# schematic.net
KiCad netlist of a schematic drawn in EAGLE
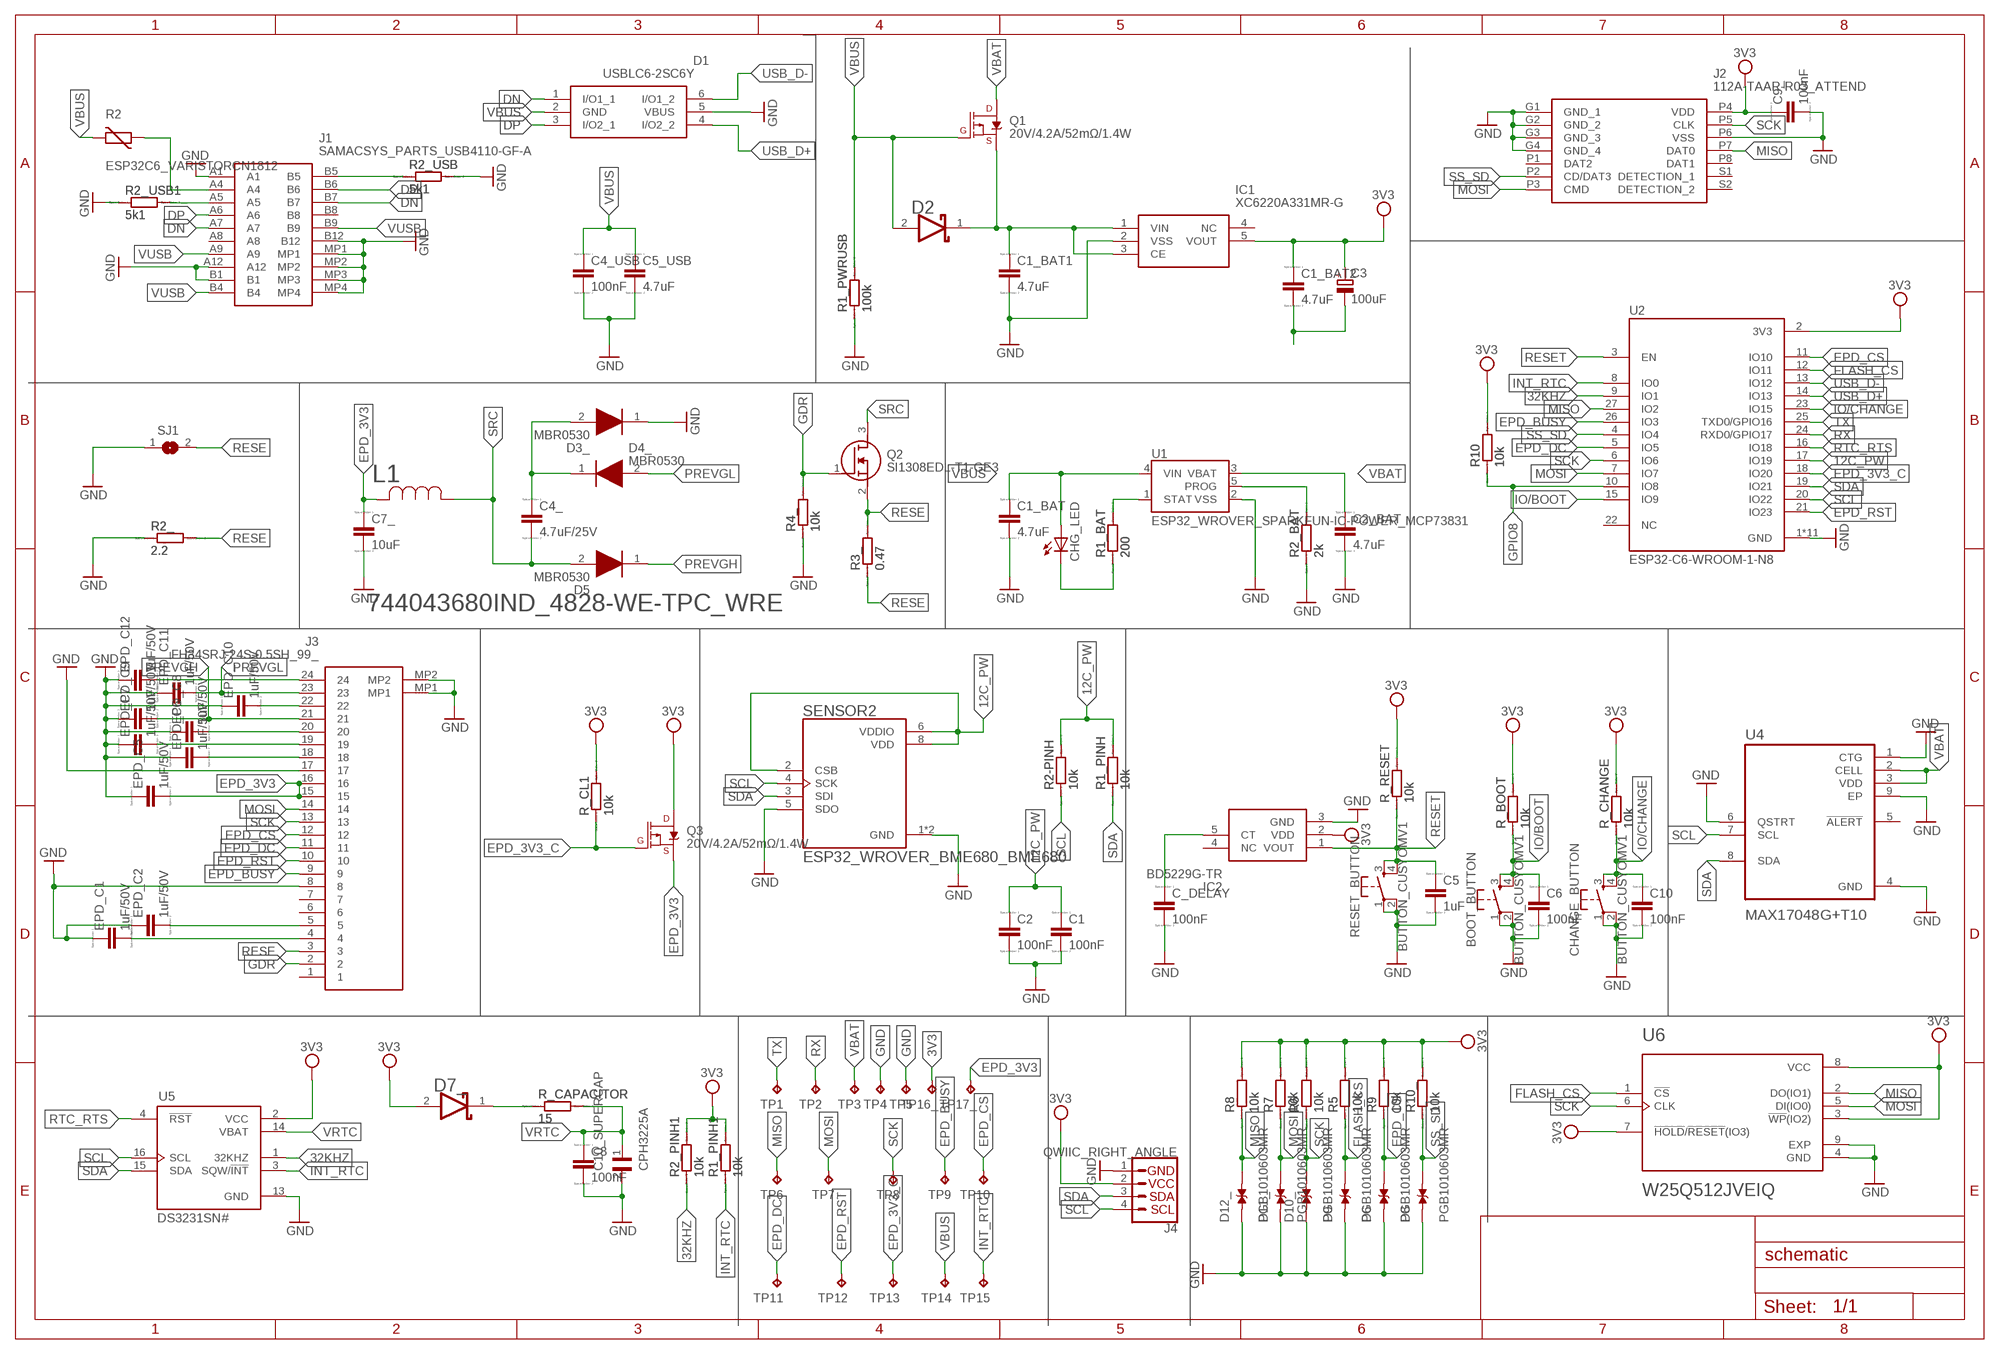
[diagram p0: schematic, sheet 1]

(export (version "E")
  (design (tool "Eeschema 10.0.6"))
  (components
    (comp (ref "BOOT_BUTTON")
      (value "BUTTON_CUSYOMV1")
      (footprint "eagle-import:MYBUTTON")
      (libsource (lib "eagle-import") (part "BUTTON_CUSYOMV1"))
    )
    (comp (ref "C1")
      (value "100nF")
      (footprint "eagle-import:EAGLE-LTSPICE_C0402")
      (libsource (lib "eagle-import") (part "EAGLE-LTSPICE_CC0402"))
    )
    (comp (ref "C1_BAT")
      (value "4.7uF")
      (footprint "eagle-import:EAGLE-LTSPICE_C0402")
      (libsource (lib "eagle-import") (part "EAGLE-LTSPICE_CC0402"))
    )
    (comp (ref "C1_BAT1")
      (value "4.7uF")
      (footprint "eagle-import:EAGLE-LTSPICE_C0402")
      (libsource (lib "eagle-import") (part "EAGLE-LTSPICE_CC0402"))
    )
    (comp (ref "C1_BAT2")
      (value "4.7uF")
      (footprint "eagle-import:EAGLE-LTSPICE_C0402")
      (libsource (lib "eagle-import") (part "EAGLE-LTSPICE_CC0402"))
    )
    (comp (ref "C2")
      (value "100nF")
      (footprint "eagle-import:EAGLE-LTSPICE_C0402")
      (libsource (lib "eagle-import") (part "EAGLE-LTSPICE_CC0402"))
    )
    (comp (ref "C2_BAT")
      (value "4.7uF")
      (footprint "eagle-import:EAGLE-LTSPICE_C0402")
      (libsource (lib "eagle-import") (part "EAGLE-LTSPICE_CC0402"))
    )
    (comp (ref "C3")
      (value "100uF")
      (footprint "eagle-import:RCL_CT3528")
      (libsource (lib "eagle-import") (part "RCL_CPOL-EUCT3528"))
    )
    (comp (ref "C4_")
      (value "4.7uF/25V")
      (footprint "eagle-import:EAGLE-LTSPICE_C0402")
      (libsource (lib "eagle-import") (part "EAGLE-LTSPICE_CC0402"))
    )
    (comp (ref "C4_USB")
      (value "100nF")
      (footprint "eagle-import:EAGLE-LTSPICE_C0402")
      (libsource (lib "eagle-import") (part "EAGLE-LTSPICE_CC0402"))
    )
    (comp (ref "C5")
      (value "1uF")
      (footprint "eagle-import:EAGLE-LTSPICE_C0402")
      (libsource (lib "eagle-import") (part "EAGLE-LTSPICE_CC0402"))
    )
    (comp (ref "C5_USB")
      (value "4.7uF")
      (footprint "eagle-import:EAGLE-LTSPICE_C0402")
      (libsource (lib "eagle-import") (part "EAGLE-LTSPICE_CC0402"))
    )
    (comp (ref "C6")
      (value "100nF")
      (footprint "eagle-import:ESP32_WROVER_EAGLE-LTSPICE_C0402")
      (libsource (lib "eagle-import") (part "ESP32_WROVER_EAGLE-LTSPICE_CC0402"))
    )
    (comp (ref "C7_")
      (value "10uF")
      (footprint "eagle-import:EAGLE-LTSPICE_C0402")
      (libsource (lib "eagle-import") (part "EAGLE-LTSPICE_CC0402"))
    )
    (comp (ref "C8")
      (value "100nF")
      (footprint "eagle-import:EAGLE-LTSPICE_C0402")
      (libsource (lib "eagle-import") (part "EAGLE-LTSPICE_CC0402"))
    )
    (comp (ref "C9_")
      (value "100nF")
      (footprint "eagle-import:ESP32_WROVER_EAGLE-LTSPICE_C0402")
      (libsource (lib "eagle-import") (part "ESP32_WROVER_EAGLE-LTSPICE_CC0402"))
    )
    (comp (ref "C10")
      (value "100nF")
      (footprint "eagle-import:ESP32_WROVER_EAGLE-LTSPICE_C0402")
      (libsource (lib "eagle-import") (part "ESP32_WROVER_EAGLE-LTSPICE_CC0402"))
    )
    (comp (ref "C10_SUPERCAP")
      (value "CPH3225A")
      (footprint "eagle-import:CAPCP3225X100N")
      (fields (field (name "MF") "Seiko Instruments"))
      (libsource (lib "eagle-import") (part "CPH3225A"))
    )
    (comp (ref "CHANGE_BUTTON")
      (value "BUTTON_CUSYOMV1")
      (footprint "eagle-import:MYBUTTON")
      (libsource (lib "eagle-import") (part "BUTTON_CUSYOMV1"))
    )
    (comp (ref "CHG_LED")
      (value "ADAFRUIT_LEDCHIP-LED0603")
      (footprint "eagle-import:ADAFRUIT_CHIP-LED0603")
      (libsource (lib "eagle-import") (part "ADAFRUIT_LEDCHIP-LED0603"))
    )
    (comp (ref "C_DELAY")
      (value "100nF")
      (footprint "eagle-import:EAGLE-LTSPICE_C0402")
      (libsource (lib "eagle-import") (part "EAGLE-LTSPICE_CC0402"))
    )
    (comp (ref "D1")
      (value "USBLC6-2SC6Y")
      (footprint "eagle-import:SOT95P280X145-6N")
      (fields (field (name "MF") "STMicroelectronics"))
      (libsource (lib "eagle-import") (part "USBLC6-2SC6Y"))
    )
    (comp (ref "D2")
      (value "ESP32_WROVER_AVX---SD0805S020S1R0_AVX_SD0805S020S1R0_0_0AVX_SD0805S020S1R0_0_0")
      (footprint "eagle-import:ESP32_WROVER_AVX---SD0805S020S1R0_AVX_SD0805S020S1R0_0")
      (fields
        (field (name "DIGIKEY_PART_NUMBER") "478-7800-1-ND")
        (field (name "MF") "AVX")
        (field (name "MOUSER_PART_NUMBER") "581-SD0805S020S1R0")
      )
      (libsource (lib "eagle-import") (part "ESP32_WROVER_AVX---SD0805S020S1R0_AVX_SD0805S020S1R0_0_0AVX_SD0805S020S1R0_0_0"))
    )
    (comp (ref "D3_")
      (value "MBR0530")
      (footprint "eagle-import:SOD3716X135N")
      (fields (field (name "MF") "ON Semiconductor"))
      (libsource (lib "eagle-import") (part "MBR0530"))
    )
    (comp (ref "D4_")
      (value "MBR0530")
      (footprint "eagle-import:SOD3716X135N")
      (fields (field (name "MF") "ON Semiconductor"))
      (libsource (lib "eagle-import") (part "MBR0530"))
    )
    (comp (ref "D5")
      (value "MBR0530")
      (footprint "eagle-import:SOD3716X135N")
      (fields (field (name "MF") "ON Semiconductor"))
      (libsource (lib "eagle-import") (part "MBR0530"))
    )
    (comp (ref "D6")
      (value "PGB1010603MR")
      (footprint "eagle-import:DIOC1608X36N")
      (fields (field (name "MF") "Littelfuse Inc."))
      (libsource (lib "eagle-import") (part "PGB1010603MR"))
    )
    (comp (ref "D7_")
      (value "ESP32_WROVER_AVX---SD0805S020S1R0_AVX_SD0805S020S1R0_0_0AVX_SD0805S020S1R0_0_0")
      (footprint "eagle-import:ESP32_WROVER_AVX---SD0805S020S1R0_AVX_SD0805S020S1R0_0")
      (fields
        (field (name "DIGIKEY_PART_NUMBER") "478-7800-1-ND")
        (field (name "MF") "AVX")
        (field (name "MOUSER_PART_NUMBER") "581-SD0805S020S1R0")
      )
      (libsource (lib "eagle-import") (part "ESP32_WROVER_AVX---SD0805S020S1R0_AVX_SD0805S020S1R0_0_0AVX_SD0805S020S1R0_0_0"))
    )
    (comp (ref "D8")
      (value "PGB1010603MR")
      (footprint "eagle-import:DIOC1608X36N")
      (fields (field (name "MF") "Littelfuse Inc."))
      (libsource (lib "eagle-import") (part "PGB1010603MR"))
    )
    (comp (ref "D9")
      (value "PGB1010603MR")
      (footprint "eagle-import:DIOC1608X36N")
      (fields (field (name "MF") "Littelfuse Inc."))
      (libsource (lib "eagle-import") (part "PGB1010603MR"))
    )
    (comp (ref "D10_")
      (value "PGB1010603MR")
      (footprint "eagle-import:DIOC1608X36N")
      (fields (field (name "MF") "Littelfuse Inc."))
      (libsource (lib "eagle-import") (part "PGB1010603MR"))
    )
    (comp (ref "D11_")
      (value "PGB1010603MR")
      (footprint "eagle-import:DIOC1608X36N")
      (fields (field (name "MF") "Littelfuse Inc."))
      (libsource (lib "eagle-import") (part "PGB1010603MR"))
    )
    (comp (ref "D12_")
      (value "PGB1010603MR")
      (footprint "eagle-import:DIOC1608X36N")
      (fields (field (name "MF") "Littelfuse Inc."))
      (libsource (lib "eagle-import") (part "PGB1010603MR"))
    )
    (comp (ref "EPD_C1")
      (value "1uF/50V")
      (footprint "eagle-import:EAGLE-LTSPICE_C0402")
      (libsource (lib "eagle-import") (part "EAGLE-LTSPICE_CC0402"))
    )
    (comp (ref "EPD_C2")
      (value "1uF/50V")
      (footprint "eagle-import:EAGLE-LTSPICE_C0402")
      (libsource (lib "eagle-import") (part "EAGLE-LTSPICE_CC0402"))
    )
    (comp (ref "EPD_C5")
      (value "1uF/50V")
      (footprint "eagle-import:EAGLE-LTSPICE_C0402")
      (libsource (lib "eagle-import") (part "EAGLE-LTSPICE_CC0402"))
    )
    (comp (ref "EPD_C6")
      (value "1uF/50V")
      (footprint "eagle-import:EAGLE-LTSPICE_C0402")
      (libsource (lib "eagle-import") (part "EAGLE-LTSPICE_CC0402"))
    )
    (comp (ref "EPD_C7")
      (value "1uF/50V")
      (footprint "eagle-import:EAGLE-LTSPICE_C0402")
      (libsource (lib "eagle-import") (part "EAGLE-LTSPICE_CC0402"))
    )
    (comp (ref "EPD_C8")
      (value "1uF/50V")
      (footprint "eagle-import:EAGLE-LTSPICE_C0402")
      (libsource (lib "eagle-import") (part "EAGLE-LTSPICE_CC0402"))
    )
    (comp (ref "EPD_C9")
      (value "1uF/50V")
      (footprint "eagle-import:EAGLE-LTSPICE_C0402")
      (libsource (lib "eagle-import") (part "EAGLE-LTSPICE_CC0402"))
    )
    (comp (ref "EPD_C10")
      (value "1uF/50V")
      (footprint "eagle-import:EAGLE-LTSPICE_C0402")
      (libsource (lib "eagle-import") (part "EAGLE-LTSPICE_CC0402"))
    )
    (comp (ref "EPD_C11")
      (value "1uF/50V")
      (footprint "eagle-import:EAGLE-LTSPICE_C0402")
      (libsource (lib "eagle-import") (part "EAGLE-LTSPICE_CC0402"))
    )
    (comp (ref "EPD_C12")
      (value "1uF/50V")
      (footprint "eagle-import:EAGLE-LTSPICE_C0402")
      (libsource (lib "eagle-import") (part "EAGLE-LTSPICE_CC0402"))
    )
    (comp (ref "IC1")
      (value "XC6220A331MR-G")
      (footprint "eagle-import:SOT95P280X120-5N")
      (fields (field (name "MOUSER_PART_NUMBER") "865-XC6220A331MR-G"))
      (libsource (lib "eagle-import") (part "XC6220A331MR-G"))
    )
    (comp (ref "IC2")
      (value "BD5229G-TR")
      (footprint "eagle-import:SOT95P280X125-5N")
      (fields (field (name "MOUSER_PART_NUMBER") "755-BD5229G-TR"))
      (libsource (lib "eagle-import") (part "BD5229G-TR"))
    )
    (comp (ref "J1")
      (value "SAMACSYS_PARTS_USB4110-GF-A")
      (footprint "eagle-import:SAMACSYS_PARTS_USB4110GFA")
      (fields
        (field (name "MANUFACTURER_PART_NUMBER") "USB4110-GF-A")
        (field (name "MOUSER_PART_NUMBER") "640-USB4110-GF-A")
      )
      (libsource (lib "eagle-import") (part "SAMACSYS_PARTS_USB4110-GF-A"))
    )
    (comp (ref "J2")
      (value "112A-TAAR-R03_ATTEND")
      (footprint "eagle-import:112ATAARR03ATTEND")
      (fields (field (name "MANUFACTURER_PART_NUMBER") "112A-TAAR-R03 ATTEND"))
      (libsource (lib "eagle-import") (part "112A-TAAR-R03_ATTEND"))
    )
    (comp (ref "J3")
      (value "FH34SRJ-24S-0.5SH_99_")
      (footprint "eagle-import:FH34SRJ24S05SH99")
      (fields
        (field (name "MANUFACTURER_PART_NUMBER") "FH34SRJ-24S-0.5SH(99)")
        (field (name "MOUSER_PART_NUMBER") "798-FH34SRJ24S05SH99")
      )
      (libsource (lib "eagle-import") (part "FH34SRJ-24S-0.5SH_99_"))
    )
    (comp (ref "J4")
      (value "QWIIC_RIGHT_ANGLE")
      (footprint "eagle-import:JST04_1MM_RA")
      (libsource (lib "eagle-import") (part "QWIIC_CONNECTORJS-1MM"))
    )
    (comp (ref "L1")
      (value "744043680IND_4828-WE-TPC_WRE")
      (footprint "eagle-import:IND_4828-WE-TPC_WRE")
      (fields
        (field (name "MANUFACTURER_PART_NUMBER") "744043680")
        (field (name "COPYRIGHT") "Copyright (C) 2024 Ultra Librarian. All rights reserved.")
      )
      (libsource (lib "eagle-import") (part "744043680IND_4828-WE-TPC_WRE"))
    )
    (comp (ref "Q1")
      (value "20V/4.2A/52mΩ/1.4W")
      (footprint "eagle-import:ESP32_WROVER_SPARKFUN-DISCRETESEMI_SOT23-3")
      (libsource (lib "eagle-import") (part "ESP32_WROVER_SPARKFUN-DISCRETESEMI_MOSFET_PCH-DMG2305UX-7"))
    )
    (comp (ref "Q2")
      (value "SI1308EDL-T1-GE3")
      (footprint "eagle-import:SOT65P210X110-3N")
      (fields (field (name "MF") "Vishay Siliconix"))
      (libsource (lib "eagle-import") (part "SI1308EDL-T1-GE3"))
    )
    (comp (ref "Q3")
      (value "20V/4.2A/52mΩ/1.4W")
      (footprint "eagle-import:ESP32_WROVER_SPARKFUN-DISCRETESEMI_SOT23-3")
      (libsource (lib "eagle-import") (part "ESP32_WROVER_SPARKFUN-DISCRETESEMI_MOSFET_PCH-DMG2305UX-7"))
    )
    (comp (ref "R1_BAT")
      (value "200")
      (footprint "eagle-import:ESP32_WROVER_EAGLE-LTSPICE_R0402")
      (libsource (lib "eagle-import") (part "ESP32_WROVER_EAGLE-LTSPICE_RR0402"))
    )
    (comp (ref "R1_PINH")
      (value "10k")
      (footprint "eagle-import:ESP32_WROVER_EAGLE-LTSPICE_R0402")
      (libsource (lib "eagle-import") (part "ESP32_WROVER_EAGLE-LTSPICE_RR0402"))
    )
    (comp (ref "R1_PINH1")
      (value "10k")
      (footprint "eagle-import:ESP32_WROVER_EAGLE-LTSPICE_R0402")
      (libsource (lib "eagle-import") (part "ESP32_WROVER_EAGLE-LTSPICE_RR0402"))
    )
    (comp (ref "R1_PWRUSB")
      (value "100k")
      (footprint "eagle-import:ESP32_WROVER_EAGLE-LTSPICE_R0402")
      (libsource (lib "eagle-import") (part "ESP32_WROVER_EAGLE-LTSPICE_RR0402"))
    )
    (comp (ref "R2")
      (value "ESP32C6_VARISTORCN1812")
      (footprint "eagle-import:ESP32C6_VARISTOR_CT_CN1812")
      (libsource (lib "eagle-import") (part "ESP32C6_VARISTORCN1812"))
    )
    (comp (ref "R2-PINH")
      (value "10k")
      (footprint "eagle-import:ESP32_WROVER_EAGLE-LTSPICE_R0402")
      (libsource (lib "eagle-import") (part "ESP32_WROVER_EAGLE-LTSPICE_RR0402"))
    )
    (comp (ref "R2_")
      (value "2.2")
      (footprint "eagle-import:ESP32_WROVER_EAGLE-LTSPICE_R0402")
      (libsource (lib "eagle-import") (part "ESP32_WROVER_EAGLE-LTSPICE_RR0402"))
    )
    (comp (ref "R2_BAT")
      (value "2k")
      (footprint "eagle-import:ESP32_WROVER_EAGLE-LTSPICE_R0402")
      (libsource (lib "eagle-import") (part "ESP32_WROVER_EAGLE-LTSPICE_RR0402"))
    )
    (comp (ref "R2_PINH1")
      (value "10k")
      (footprint "eagle-import:ESP32_WROVER_EAGLE-LTSPICE_R0402")
      (libsource (lib "eagle-import") (part "ESP32_WROVER_EAGLE-LTSPICE_RR0402"))
    )
    (comp (ref "R2_USB")
      (value "5k1")
      (footprint "eagle-import:ESP32_WROVER_EAGLE-LTSPICE_R0402")
      (libsource (lib "eagle-import") (part "ESP32_WROVER_EAGLE-LTSPICE_RR0402"))
    )
    (comp (ref "R2_USB1")
      (value "5k1")
      (footprint "eagle-import:ESP32_WROVER_EAGLE-LTSPICE_R0402")
      (libsource (lib "eagle-import") (part "ESP32_WROVER_EAGLE-LTSPICE_RR0402"))
    )
    (comp (ref "R3_")
      (value "0.47")
      (footprint "eagle-import:ESP32_WROVER_EAGLE-LTSPICE_R0402")
      (libsource (lib "eagle-import") (part "ESP32_WROVER_EAGLE-LTSPICE_RR0402"))
    )
    (comp (ref "R4_")
      (value "10k")
      (footprint "eagle-import:ESP32_WROVER_EAGLE-LTSPICE_R0402")
      (libsource (lib "eagle-import") (part "ESP32_WROVER_EAGLE-LTSPICE_RR0402"))
    )
    (comp (ref "R5")
      (value "10k")
      (footprint "eagle-import:ESP32_WROVER_EAGLE-LTSPICE_R0402")
      (libsource (lib "eagle-import") (part "ESP32_WROVER_EAGLE-LTSPICE_RR0402"))
    )
    (comp (ref "R6")
      (value "10k")
      (footprint "eagle-import:ESP32_WROVER_EAGLE-LTSPICE_R0402")
      (libsource (lib "eagle-import") (part "ESP32_WROVER_EAGLE-LTSPICE_RR0402"))
    )
    (comp (ref "R7")
      (value "10k")
      (footprint "eagle-import:ESP32_WROVER_EAGLE-LTSPICE_R0402")
      (libsource (lib "eagle-import") (part "ESP32_WROVER_EAGLE-LTSPICE_RR0402"))
    )
    (comp (ref "R8")
      (value "10k")
      (footprint "eagle-import:ESP32_WROVER_EAGLE-LTSPICE_R0402")
      (libsource (lib "eagle-import") (part "ESP32_WROVER_EAGLE-LTSPICE_RR0402"))
    )
    (comp (ref "R9")
      (value "10k")
      (footprint "eagle-import:ESP32_WROVER_EAGLE-LTSPICE_R0402")
      (libsource (lib "eagle-import") (part "ESP32_WROVER_EAGLE-LTSPICE_RR0402"))
    )
    (comp (ref "R10")
      (value "10k")
      (footprint "eagle-import:ESP32_WROVER_EAGLE-LTSPICE_R0402")
      (libsource (lib "eagle-import") (part "ESP32_WROVER_EAGLE-LTSPICE_RR0402"))
    )
    (comp (ref "R10_")
      (value "10k")
      (footprint "eagle-import:ESP32_WROVER_EAGLE-LTSPICE_R0402")
      (libsource (lib "eagle-import") (part "ESP32_WROVER_EAGLE-LTSPICE_RR0402"))
    )
    (comp (ref "RESET_BUTTON")
      (value "BUTTON_CUSYOMV1")
      (footprint "eagle-import:MYBUTTON")
      (libsource (lib "eagle-import") (part "BUTTON_CUSYOMV1"))
    )
    (comp (ref "R_BOOT")
      (value "10k")
      (footprint "eagle-import:ESP32_WROVER_EAGLE-LTSPICE_R0402")
      (libsource (lib "eagle-import") (part "ESP32_WROVER_EAGLE-LTSPICE_RR0402"))
    )
    (comp (ref "R_CAPACITOR")
      (value "15")
      (footprint "eagle-import:ESP32_WROVER_EAGLE-LTSPICE_R0402")
      (libsource (lib "eagle-import") (part "ESP32_WROVER_EAGLE-LTSPICE_RR0402"))
    )
    (comp (ref "R_CHANGE")
      (value "10k")
      (footprint "eagle-import:ESP32_WROVER_EAGLE-LTSPICE_R0402")
      (libsource (lib "eagle-import") (part "ESP32_WROVER_EAGLE-LTSPICE_RR0402"))
    )
    (comp (ref "R_CL1")
      (value "10k")
      (footprint "eagle-import:ESP32_WROVER_EAGLE-LTSPICE_R0402")
      (libsource (lib "eagle-import") (part "ESP32_WROVER_EAGLE-LTSPICE_RR0402"))
    )
    (comp (ref "R_RESET")
      (value "10k")
      (footprint "eagle-import:ESP32_WROVER_EAGLE-LTSPICE_R0402")
      (libsource (lib "eagle-import") (part "ESP32_WROVER_EAGLE-LTSPICE_RR0402"))
    )
    (comp (ref "SENSOR2")
      (value "ESP32_WROVER_BME680_BME680")
      (footprint "eagle-import:ESP32_WROVER_BME680_PSON80P300X300X100-8N")
      (fields (field (name "MF") "Bosch Sensortec") (field (name "MP") "BME680"))
      (libsource (lib "eagle-import") (part "ESP32_WROVER_BME680_BME680"))
    )
    (comp (ref "SJ1") (value "SJ") (footprint "eagle-import:SJ") (libsource (lib "eagle-import") (part "SJ")))
    (comp (ref "TP1")
      (value "TPTP20R")
      (footprint "eagle-import:TP20R")
      (libsource (lib "eagle-import") (part "TPTP20R"))
    )
    (comp (ref "TP2")
      (value "TPTP20R")
      (footprint "eagle-import:TP20R")
      (libsource (lib "eagle-import") (part "TPTP20R"))
    )
    (comp (ref "TP3")
      (value "TPTP20R")
      (footprint "eagle-import:TP20R")
      (libsource (lib "eagle-import") (part "TPTP20R"))
    )
    (comp (ref "TP4")
      (value "TPTP20R")
      (footprint "eagle-import:TP20R")
      (libsource (lib "eagle-import") (part "TPTP20R"))
    )
    (comp (ref "TP5")
      (value "TPTP20R")
      (footprint "eagle-import:TP20R")
      (libsource (lib "eagle-import") (part "TPTP20R"))
    )
    (comp (ref "TP6")
      (value "TPTP20R")
      (footprint "eagle-import:TP20R")
      (libsource (lib "eagle-import") (part "TPTP20R"))
    )
    (comp (ref "TP7")
      (value "TPTP20R")
      (footprint "eagle-import:TP20R")
      (libsource (lib "eagle-import") (part "TPTP20R"))
    )
    (comp (ref "TP8")
      (value "TPTP20R")
      (footprint "eagle-import:TP20R")
      (libsource (lib "eagle-import") (part "TPTP20R"))
    )
    (comp (ref "TP9")
      (value "TPTP20R")
      (footprint "eagle-import:TP20R")
      (libsource (lib "eagle-import") (part "TPTP20R"))
    )
    (comp (ref "TP10")
      (value "TPTP20R")
      (footprint "eagle-import:TP20R")
      (libsource (lib "eagle-import") (part "TPTP20R"))
    )
    (comp (ref "TP11")
      (value "TPTP20R")
      (footprint "eagle-import:TP20R")
      (libsource (lib "eagle-import") (part "TPTP20R"))
    )
    (comp (ref "TP12")
      (value "TPTP20R")
      (footprint "eagle-import:TP20R")
      (libsource (lib "eagle-import") (part "TPTP20R"))
    )
    (comp (ref "TP13")
      (value "TPTP20R")
      (footprint "eagle-import:TP20R")
      (libsource (lib "eagle-import") (part "TPTP20R"))
    )
    (comp (ref "TP14")
      (value "TPTP20R")
      (footprint "eagle-import:TP20R")
      (libsource (lib "eagle-import") (part "TPTP20R"))
    )
    (comp (ref "TP15")
      (value "TPTP20R")
      (footprint "eagle-import:TP20R")
      (libsource (lib "eagle-import") (part "TPTP20R"))
    )
    (comp (ref "TP16_")
      (value "TPTP20R")
      (footprint "eagle-import:TP20R")
      (libsource (lib "eagle-import") (part "TPTP20R"))
    )
    (comp (ref "TP17_")
      (value "TPTP20R")
      (footprint "eagle-import:TP20R")
      (libsource (lib "eagle-import") (part "TPTP20R"))
    )
    (comp (ref "U1")
      (value "ESP32_WROVER_SPARKFUN-IC-POWER_MCP73831")
      (footprint "eagle-import:ESP32_WROVER_SPARKFUN-IC-POWER_SOT23-5")
      (libsource (lib "eagle-import") (part "ESP32_WROVER_SPARKFUN-IC-POWER_MCP73831"))
    )
    (comp (ref "U2")
      (value "ESP32-C6-WROOM-1-N8")
      (footprint "eagle-import:XCVR_ESP32-C6-WROOM-1-N8")
      (fields (field (name "MF") "Espressif Systems"))
      (libsource (lib "eagle-import") (part "ESP32-C6-WROOM-1-N8"))
    )
    (comp (ref "U4")
      (value "MAX17048G+T10")
      (footprint "eagle-import:SON50P200X200X80-9N")
      (fields (field (name "MF") "Analog Devices"))
      (libsource (lib "eagle-import") (part "MAX17048G+T10"))
    )
    (comp (ref "U5")
      (value "DS3231SN#")
      (footprint "eagle-import:SOIC127P1032X265-16N")
      (fields (field (name "MF") "Analog Devices"))
      (libsource (lib "eagle-import") (part "DS3231SN#"))
    )
    (comp (ref "U6")
      (value "W25Q512JVEIQ")
      (footprint "eagle-import:SON127P600X800X80-9N")
      (fields (field (name "MF") "Winbond Electronics"))
      (libsource (lib "eagle-import") (part "W25Q512JVEIQ"))
    )
  )
  (nets
    (net (code "1") (name "3V3") (class "Default")
      (node (ref "C1_BAT2") (pin "1") (pinfunction "1_1") (pintype "passive"))
      (node (ref "C3") (pin "+") (pinfunction "+_+") (pintype "passive"))
      (node (ref "C9_") (pin "1") (pinfunction "1_1") (pintype "passive"))
      (node (ref "D7_") (pin "2") (pinfunction "ANODE_2") (pintype "bidirectional"))
      (node (ref "IC1") (pin "5") (pinfunction "VOUT_5") (pintype "bidirectional"))
      (node (ref "IC2") (pin "2") (pinfunction "VDD_2") (pintype "bidirectional"))
      (node (ref "J2") (pin "P4") (pinfunction "VDD_P4") (pintype "bidirectional"))
      (node (ref "J4") (pin "2") (pinfunction "2_2") (pintype "power_in"))
      (node (ref "Q3") (pin "3") (pinfunction "D_3") (pintype "bidirectional"))
      (node (ref "R10") (pin "2") (pinfunction "2_2") (pintype "passive"))
      (node (ref "R10_") (pin "2") (pinfunction "2_2") (pintype "passive"))
      (node (ref "R1_PINH1") (pin "2") (pinfunction "2_2") (pintype "passive"))
      (node (ref "R2_PINH1") (pin "2") (pinfunction "2_2") (pintype "passive"))
      (node (ref "R5") (pin "2") (pinfunction "2_2") (pintype "passive"))
      (node (ref "R6") (pin "2") (pinfunction "2_2") (pintype "passive"))
      (node (ref "R7") (pin "2") (pinfunction "2_2") (pintype "passive"))
      (node (ref "R8") (pin "2") (pinfunction "2_2") (pintype "passive"))
      (node (ref "R9") (pin "2") (pinfunction "2_2") (pintype "passive"))
      (node (ref "R_BOOT") (pin "2") (pinfunction "2_2") (pintype "passive"))
      (node (ref "R_CHANGE") (pin "2") (pinfunction "2_2") (pintype "passive"))
      (node (ref "R_CL1") (pin "2") (pinfunction "2_2") (pintype "passive"))
      (node (ref "R_RESET") (pin "2") (pinfunction "2_2") (pintype "passive"))
      (node (ref "TP16_") (pin "TP") (pinfunction "TP_TP") (pintype "input"))
      (node (ref "U2") (pin "2") (pinfunction "3V3_2") (pintype "power_in"))
      (node (ref "U5") (pin "2") (pinfunction "VCC_2") (pintype "power_in"))
      (node (ref "U6") (pin "3") (pinfunction "~{WP}(IO2)_3") (pintype "bidirectional"))
      (node (ref "U6") (pin "7") (pinfunction "~{HOLD}/~{RESET}(IO3)_7") (pintype "bidirectional"))
      (node (ref "U6") (pin "8") (pinfunction "VCC_8") (pintype "power_in"))
    )
    (net (code "2") (name "12C_PW") (class "Default")
      (node (ref "C1") (pin "1") (pinfunction "1_1") (pintype "passive"))
      (node (ref "C2") (pin "1") (pinfunction "1_1") (pintype "passive"))
      (node (ref "R1_PINH") (pin "2") (pinfunction "2_2") (pintype "passive"))
      (node (ref "R2-PINH") (pin "2") (pinfunction "2_2") (pintype "passive"))
      (node (ref "SENSOR2") (pin "2") (pinfunction "CSB_2") (pintype "input"))
      (node (ref "SENSOR2") (pin "6") (pinfunction "VDDIO_6") (pintype "power_in"))
      (node (ref "SENSOR2") (pin "8") (pinfunction "VDD_8") (pintype "power_in"))
      (node (ref "U2") (pin "17") (pinfunction "IO19_17") (pintype "bidirectional"))
    )
    (net (code "3") (name "32KHZ") (class "Default")
      (node (ref "R2_PINH1") (pin "1") (pinfunction "1_1") (pintype "passive"))
      (node (ref "U2") (pin "9") (pinfunction "IO1_9") (pintype "bidirectional"))
      (node (ref "U5") (pin "1") (pinfunction "32KHZ_1") (pintype "output"))
    )
    (net (code "4") (name "DN") (class "Default")
      (node (ref "D1") (pin "1") (pinfunction "I/O1_1_1") (pintype "bidirectional"))
      (node (ref "J1") (pin "A7") (pinfunction "A7_A7") (pintype "bidirectional"))
      (node (ref "J1") (pin "B7") (pinfunction "B7_B7") (pintype "bidirectional"))
    )
    (net (code "5") (name "DP") (class "Default")
      (node (ref "D1") (pin "3") (pinfunction "I/O2_1_3") (pintype "bidirectional"))
      (node (ref "J1") (pin "A6") (pinfunction "A6_A6") (pintype "bidirectional"))
      (node (ref "J1") (pin "B6") (pinfunction "B6_B6") (pintype "bidirectional"))
    )
    (net (code "6") (name "EPD_3V3") (class "Default")
      (node (ref "C7_") (pin "1") (pinfunction "1_1") (pintype "passive"))
      (node (ref "EPD_C5") (pin "2") (pinfunction "2_2") (pintype "passive"))
      (node (ref "J3") (pin "15") (pinfunction "15_15") (pintype "bidirectional"))
      (node (ref "J3") (pin "16") (pinfunction "16_16") (pintype "bidirectional"))
      (node (ref "L1") (pin "2") (pinfunction "2_2") (pintype "passive"))
      (node (ref "Q3") (pin "2") (pinfunction "S_2") (pintype "bidirectional"))
      (node (ref "TP17_") (pin "TP") (pinfunction "TP_TP") (pintype "input"))
    )
    (net (code "7") (name "EPD_3V3_C") (class "Default")
      (node (ref "Q3") (pin "1") (pinfunction "G_1") (pintype "bidirectional"))
      (node (ref "R_CL1") (pin "1") (pinfunction "1_1") (pintype "passive"))
      (node (ref "TP13") (pin "TP") (pinfunction "TP_TP") (pintype "input"))
      (node (ref "U2") (pin "18") (pinfunction "IO20_18") (pintype "bidirectional"))
    )
    (net (code "8") (name "EPD_BUSY") (class "Default")
      (node (ref "J3") (pin "9") (pinfunction "9_9") (pintype "bidirectional"))
      (node (ref "TP9") (pin "TP") (pinfunction "TP_TP") (pintype "input"))
      (node (ref "U2") (pin "26") (pinfunction "IO3_26") (pintype "bidirectional"))
    )
    (net (code "9") (name "EPD_CS") (class "Default")
      (node (ref "D6") (pin "2") (pinfunction "2_2") (pintype "passive"))
      (node (ref "J3") (pin "12") (pinfunction "12_12") (pintype "bidirectional"))
      (node (ref "R9") (pin "1") (pinfunction "1_1") (pintype "passive"))
      (node (ref "TP10") (pin "TP") (pinfunction "TP_TP") (pintype "input"))
      (node (ref "U2") (pin "11") (pinfunction "IO10_11") (pintype "bidirectional"))
    )
    (net (code "10") (name "EPD_DC") (class "Default")
      (node (ref "J3") (pin "11") (pinfunction "11_11") (pintype "bidirectional"))
      (node (ref "TP11") (pin "TP") (pinfunction "TP_TP") (pintype "input"))
      (node (ref "U2") (pin "5") (pinfunction "IO5_5") (pintype "bidirectional"))
    )
    (net (code "11") (name "EPD_RST") (class "Default")
      (node (ref "J3") (pin "10") (pinfunction "10_10") (pintype "bidirectional"))
      (node (ref "TP12") (pin "TP") (pinfunction "TP_TP") (pintype "input"))
      (node (ref "U2") (pin "21") (pinfunction "IO23_21") (pintype "bidirectional"))
    )
    (net (code "12") (name "FLASH_CS") (class "Default")
      (node (ref "D9") (pin "2") (pinfunction "2_2") (pintype "passive"))
      (node (ref "R5") (pin "1") (pinfunction "1_1") (pintype "passive"))
      (node (ref "U2") (pin "12") (pinfunction "IO11_12") (pintype "bidirectional"))
      (node (ref "U6") (pin "1") (pinfunction "~{CS}_1") (pintype "input"))
    )
    (net (code "13") (name "GDR") (class "Default")
      (node (ref "J3") (pin "2") (pinfunction "2_2") (pintype "bidirectional"))
      (node (ref "Q2") (pin "1") (pinfunction "G_1") (pintype "bidirectional"))
      (node (ref "R4_") (pin "2") (pinfunction "2_2") (pintype "passive"))
    )
    (net (code "14") (name "GND") (class "Default")
      (node (ref "BOOT_BUTTON") (pin "1") (pinfunction "1_1") (pintype "passive"))
      (node (ref "BOOT_BUTTON") (pin "2") (pinfunction "2_2") (pintype "passive"))
      (node (ref "C1") (pin "2") (pinfunction "2_2") (pintype "passive"))
      (node (ref "C10") (pin "2") (pinfunction "2_2") (pintype "passive"))
      (node (ref "C10_SUPERCAP") (pin "2") (pinfunction "2_2") (pintype "passive"))
      (node (ref "C1_BAT") (pin "2") (pinfunction "2_2") (pintype "passive"))
      (node (ref "C1_BAT1") (pin "2") (pinfunction "2_2") (pintype "passive"))
      (node (ref "C2") (pin "2") (pinfunction "2_2") (pintype "passive"))
      (node (ref "C2_BAT") (pin "2") (pinfunction "2_2") (pintype "passive"))
      (node (ref "C4_USB") (pin "2") (pinfunction "2_2") (pintype "passive"))
      (node (ref "C5") (pin "2") (pinfunction "2_2") (pintype "passive"))
      (node (ref "C5_USB") (pin "2") (pinfunction "2_2") (pintype "passive"))
      (node (ref "C6") (pin "2") (pinfunction "2_2") (pintype "passive"))
      (node (ref "C7_") (pin "2") (pinfunction "2_2") (pintype "passive"))
      (node (ref "C8") (pin "2") (pinfunction "2_2") (pintype "passive"))
      (node (ref "C9_") (pin "2") (pinfunction "2_2") (pintype "passive"))
      (node (ref "CHANGE_BUTTON") (pin "1") (pinfunction "1_1") (pintype "passive"))
      (node (ref "CHANGE_BUTTON") (pin "2") (pinfunction "2_2") (pintype "passive"))
      (node (ref "C_DELAY") (pin "2") (pinfunction "2_2") (pintype "passive"))
      (node (ref "D1") (pin "5") (pinfunction "VBUS_5") (pintype "bidirectional"))
      (node (ref "D10_") (pin "1") (pinfunction "1_1") (pintype "passive"))
      (node (ref "D11_") (pin "1") (pinfunction "1_1") (pintype "passive"))
      (node (ref "D12_") (pin "1") (pinfunction "1_1") (pintype "passive"))
      (node (ref "D3_") (pin "1") (pinfunction "K_1") (pintype "bidirectional"))
      (node (ref "D6") (pin "1") (pinfunction "1_1") (pintype "passive"))
      (node (ref "D8") (pin "1") (pinfunction "1_1") (pintype "passive"))
      (node (ref "D9") (pin "1") (pinfunction "1_1") (pintype "passive"))
      (node (ref "EPD_C1") (pin "1") (pinfunction "1_1") (pintype "passive"))
      (node (ref "EPD_C10") (pin "1") (pinfunction "1_1") (pintype "passive"))
      (node (ref "EPD_C11") (pin "1") (pinfunction "1_1") (pintype "passive"))
      (node (ref "EPD_C12") (pin "1") (pinfunction "1_1") (pintype "passive"))
      (node (ref "EPD_C2") (pin "1") (pinfunction "1_1") (pintype "passive"))
      (node (ref "EPD_C5") (pin "1") (pinfunction "1_1") (pintype "passive"))
      (node (ref "EPD_C6") (pin "1") (pinfunction "1_1") (pintype "passive"))
      (node (ref "EPD_C7") (pin "1") (pinfunction "1_1") (pintype "passive"))
      (node (ref "EPD_C8") (pin "1") (pinfunction "1_1") (pintype "passive"))
      (node (ref "EPD_C9") (pin "1") (pinfunction "1_1") (pintype "passive"))
      (node (ref "IC1") (pin "2") (pinfunction "VSS_2") (pintype "bidirectional"))
      (node (ref "IC2") (pin "3") (pinfunction "GND_3") (pintype "bidirectional"))
      (node (ref "J1") (pin "A1") (pinfunction "A1_A1") (pintype "bidirectional"))
      (node (ref "J1") (pin "A12") (pinfunction "A12_A12") (pintype "bidirectional"))
      (node (ref "J1") (pin "B1") (pinfunction "B1_B1") (pintype "bidirectional"))
      (node (ref "J1") (pin "B12") (pinfunction "B12_B12") (pintype "bidirectional"))
      (node (ref "J1") (pin "MP1") (pinfunction "MP1_MP1") (pintype "bidirectional"))
      (node (ref "J1") (pin "MP2") (pinfunction "MP2_MP2") (pintype "bidirectional"))
      (node (ref "J1") (pin "MP3") (pinfunction "MP3_MP3") (pintype "bidirectional"))
      (node (ref "J1") (pin "MP4") (pinfunction "MP4_MP4") (pintype "bidirectional"))
      (node (ref "J2") (pin "G1") (pinfunction "GND_1_G1") (pintype "bidirectional"))
      (node (ref "J2") (pin "G2") (pinfunction "GND_2_G2") (pintype "bidirectional"))
      (node (ref "J2") (pin "G3") (pinfunction "GND_3_G3") (pintype "bidirectional"))
      (node (ref "J2") (pin "G4") (pinfunction "GND_4_G4") (pintype "bidirectional"))
      (node (ref "J2") (pin "P6") (pinfunction "VSS_P6") (pintype "bidirectional"))
      (node (ref "J3") (pin "17") (pinfunction "17_17") (pintype "bidirectional"))
      (node (ref "J3") (pin "8") (pinfunction "8_8") (pintype "bidirectional"))
      (node (ref "J3") (pin "MP1") (pinfunction "MP1_MP1") (pintype "bidirectional"))
      (node (ref "J3") (pin "MP2") (pinfunction "MP2_MP2") (pintype "bidirectional"))
      (node (ref "J4") (pin "1") (pinfunction "1_1") (pintype "power_in"))
      (node (ref "R1_PWRUSB") (pin "1") (pinfunction "1_1") (pintype "passive"))
      (node (ref "R2_") (pin "1") (pinfunction "1_1") (pintype "passive"))
      (node (ref "R2_BAT") (pin "1") (pinfunction "1_1") (pintype "passive"))
      (node (ref "R2_USB") (pin "2") (pinfunction "2_2") (pintype "passive"))
      (node (ref "R2_USB1") (pin "1") (pinfunction "1_1") (pintype "passive"))
      (node (ref "R4_") (pin "1") (pinfunction "1_1") (pintype "passive"))
      (node (ref "RESET_BUTTON") (pin "1") (pinfunction "1_1") (pintype "passive"))
      (node (ref "RESET_BUTTON") (pin "2") (pinfunction "2_2") (pintype "passive"))
      (node (ref "SENSOR2") (pin "1") (pinfunction "GND_1") (pintype "power_in"))
      (node (ref "SENSOR2") (pin "5") (pinfunction "SDO_5") (pintype "bidirectional"))
      (node (ref "SENSOR2") (pin "7") (pinfunction "GND_7") (pintype "power_in"))
      (node (ref "SJ1") (pin "1") (pinfunction "1_1") (pintype "passive"))
      (node (ref "TP4") (pin "TP") (pinfunction "TP_TP") (pintype "input"))
      (node (ref "TP5") (pin "TP") (pinfunction "TP_TP") (pintype "input"))
      (node (ref "U1") (pin "2") (pinfunction "VSS_2") (pintype "power_in"))
      (node (ref "U2") (pin "1") (pinfunction "GND_1") (pintype "power_in"))
      (node (ref "U2") (pin "28") (pinfunction "GND_28") (pintype "power_in"))
      (node (ref "U2") (pin "29_1") (pinfunction "GND_29_1") (pintype "power_in"))
      (node (ref "U2") (pin "29_2") (pinfunction "GND_29_2") (pintype "power_in"))
      (node (ref "U2") (pin "29_3") (pinfunction "GND_29_3") (pintype "power_in"))
      (node (ref "U2") (pin "29_4") (pinfunction "GND_29_4") (pintype "power_in"))
      (node (ref "U2") (pin "29_5") (pinfunction "GND_29_5") (pintype "power_in"))
      (node (ref "U2") (pin "29_6") (pinfunction "GND_29_6") (pintype "power_in"))
      (node (ref "U2") (pin "29_7") (pinfunction "GND_29_7") (pintype "power_in"))
      (node (ref "U2") (pin "29_8") (pinfunction "GND_29_8") (pintype "power_in"))
      (node (ref "U2") (pin "29_9") (pinfunction "GND_29_9") (pintype "power_in"))
      (node (ref "U4") (pin "1") (pinfunction "CTG_1") (pintype "power_in"))
      (node (ref "U4") (pin "4") (pinfunction "GND_4") (pintype "power_in"))
      (node (ref "U4") (pin "6") (pinfunction "QSTRT_6") (pintype "input"))
      (node (ref "U4") (pin "9") (pinfunction "EP_9") (pintype "power_in"))
      (node (ref "U5") (pin "13") (pinfunction "GND_13") (pintype "power_in"))
      (node (ref "U6") (pin "4") (pinfunction "GND_4") (pintype "power_in"))
      (node (ref "U6") (pin "9") (pinfunction "EXP_9") (pintype "passive"))
    )
    (net (code "15") (name "GPIO8") (class "Default")
      (node (ref "R10") (pin "1") (pinfunction "1_1") (pintype "passive"))
      (node (ref "U2") (pin "10") (pinfunction "IO8_10") (pintype "bidirectional"))
    )
    (net (code "16") (name "INT_RTC") (class "Default")
      (node (ref "R1_PINH1") (pin "1") (pinfunction "1_1") (pintype "passive"))
      (node (ref "TP15") (pin "TP") (pinfunction "TP_TP") (pintype "input"))
      (node (ref "U2") (pin "8") (pinfunction "IO0_8") (pintype "bidirectional"))
      (node (ref "U5") (pin "3") (pinfunction "SQW/~{INT}_3") (pintype "output"))
    )
    (net (code "17") (name "IO{slash}BOOT") (class "Default")
      (node (ref "BOOT_BUTTON") (pin "3") (pinfunction "3_3") (pintype "passive"))
      (node (ref "BOOT_BUTTON") (pin "4") (pinfunction "4_4") (pintype "passive"))
      (node (ref "C6") (pin "1") (pinfunction "1_1") (pintype "passive"))
      (node (ref "R_BOOT") (pin "1") (pinfunction "1_1") (pintype "passive"))
      (node (ref "U2") (pin "15") (pinfunction "IO9_15") (pintype "bidirectional"))
    )
    (net (code "18") (name "IO{slash}CHANGE") (class "Default")
      (node (ref "C10") (pin "1") (pinfunction "1_1") (pintype "passive"))
      (node (ref "CHANGE_BUTTON") (pin "3") (pinfunction "3_3") (pintype "passive"))
      (node (ref "CHANGE_BUTTON") (pin "4") (pinfunction "4_4") (pintype "passive"))
      (node (ref "R_CHANGE") (pin "1") (pinfunction "1_1") (pintype "passive"))
      (node (ref "U2") (pin "23") (pinfunction "IO15_23") (pintype "bidirectional"))
    )
    (net (code "19") (name "MISO") (class "Default")
      (node (ref "D12_") (pin "2") (pinfunction "2_2") (pintype "passive"))
      (node (ref "J2") (pin "P7") (pinfunction "DAT0_P7") (pintype "bidirectional"))
      (node (ref "R8") (pin "1") (pinfunction "1_1") (pintype "passive"))
      (node (ref "TP6") (pin "TP") (pinfunction "TP_TP") (pintype "input"))
      (node (ref "U2") (pin "27") (pinfunction "IO2_27") (pintype "bidirectional"))
      (node (ref "U6") (pin "2") (pinfunction "DO(IO1)_2") (pintype "bidirectional"))
    )
    (net (code "20") (name "MOSI") (class "Default")
      (node (ref "D11_") (pin "2") (pinfunction "2_2") (pintype "passive"))
      (node (ref "J2") (pin "P3") (pinfunction "CMD_P3") (pintype "bidirectional"))
      (node (ref "J3") (pin "14") (pinfunction "14_14") (pintype "bidirectional"))
      (node (ref "R7") (pin "1") (pinfunction "1_1") (pintype "passive"))
      (node (ref "TP7") (pin "TP") (pinfunction "TP_TP") (pintype "input"))
      (node (ref "U2") (pin "7") (pinfunction "IO7_7") (pintype "bidirectional"))
      (node (ref "U6") (pin "5") (pinfunction "DI(IO0)_5") (pintype "bidirectional"))
    )
    (net (code "21") (name "Net-(C1_BAT2-Pad2)") (class "Default")
      (node (ref "C1_BAT2") (pin "2") (pinfunction "2_2") (pintype "passive"))
      (node (ref "C3") (pin "-") (pinfunction "-_-") (pintype "passive"))
    )
    (net (code "22") (name "Net-(CHG_LED-PadC)") (class "Default")
      (node (ref "CHG_LED") (pin "C") (pinfunction "C_C") (pintype "passive"))
      (node (ref "R1_BAT") (pin "1") (pinfunction "1_1") (pintype "passive"))
    )
    (net (code "23") (name "Net-(D2-CATHODE)") (class "Default")
      (node (ref "C1_BAT1") (pin "1") (pinfunction "1_1") (pintype "passive"))
      (node (ref "D2") (pin "1") (pinfunction "CATHODE_1") (pintype "bidirectional"))
      (node (ref "IC1") (pin "1") (pinfunction "VIN_1") (pintype "bidirectional"))
      (node (ref "IC1") (pin "3") (pinfunction "CE_3") (pintype "bidirectional"))
      (node (ref "Q1") (pin "2") (pinfunction "S_2") (pintype "bidirectional"))
    )
    (net (code "24") (name "Net-(D3_-A)") (class "Default")
      (node (ref "C4_") (pin "1") (pinfunction "1_1") (pintype "passive"))
      (node (ref "D3_") (pin "2") (pinfunction "A_2") (pintype "bidirectional"))
      (node (ref "D4_") (pin "1") (pinfunction "K_1") (pintype "bidirectional"))
    )
    (net (code "25") (name "Net-(D7_-CATHODE)") (class "Default")
      (node (ref "D7_") (pin "1") (pinfunction "CATHODE_1") (pintype "bidirectional"))
      (node (ref "R_CAPACITOR") (pin "1") (pinfunction "1_1") (pintype "passive"))
    )
    (net (code "26") (name "Net-(EPD_C1-Pad2)") (class "Default")
      (node (ref "EPD_C1") (pin "2") (pinfunction "2_2") (pintype "passive"))
      (node (ref "J3") (pin "4") (pinfunction "4_4") (pintype "bidirectional"))
    )
    (net (code "27") (name "Net-(EPD_C2-Pad2)") (class "Default")
      (node (ref "EPD_C2") (pin "2") (pinfunction "2_2") (pintype "passive"))
      (node (ref "J3") (pin "5") (pinfunction "5_5") (pintype "bidirectional"))
    )
    (net (code "28") (name "Net-(EPD_C6-Pad2)") (class "Default")
      (node (ref "EPD_C6") (pin "2") (pinfunction "2_2") (pintype "passive"))
      (node (ref "J3") (pin "18") (pinfunction "18_18") (pintype "bidirectional"))
    )
    (net (code "29") (name "Net-(EPD_C7-Pad2)") (class "Default")
      (node (ref "EPD_C7") (pin "2") (pinfunction "2_2") (pintype "passive"))
      (node (ref "J3") (pin "19") (pinfunction "19_19") (pintype "bidirectional"))
    )
    (net (code "30") (name "Net-(EPD_C8-Pad2)") (class "Default")
      (node (ref "EPD_C8") (pin "2") (pinfunction "2_2") (pintype "passive"))
      (node (ref "J3") (pin "20") (pinfunction "20_20") (pintype "bidirectional"))
    )
    (net (code "31") (name "Net-(EPD_C10-Pad2)") (class "Default")
      (node (ref "EPD_C10") (pin "2") (pinfunction "2_2") (pintype "passive"))
      (node (ref "J3") (pin "22") (pinfunction "22_22") (pintype "bidirectional"))
    )
    (net (code "32") (name "Net-(EPD_C12-Pad2)") (class "Default")
      (node (ref "EPD_C12") (pin "2") (pinfunction "2_2") (pintype "passive"))
      (node (ref "J3") (pin "24") (pinfunction "24_24") (pintype "bidirectional"))
    )
    (net (code "33") (name "Net-(IC2-CT)") (class "Default")
      (node (ref "C_DELAY") (pin "1") (pinfunction "1_1") (pintype "passive"))
      (node (ref "IC2") (pin "5") (pinfunction "CT_5") (pintype "bidirectional"))
    )
    (net (code "34") (name "Net-(J1-PadA4)") (class "Default")
      (node (ref "J1") (pin "A4") (pinfunction "A4_A4") (pintype "bidirectional"))
      (node (ref "R2") (pin "1") (pinfunction "1_1") (pintype "passive"))
    )
    (net (code "35") (name "Net-(J1-PadA5)") (class "Default")
      (node (ref "J1") (pin "A5") (pinfunction "A5_A5") (pintype "bidirectional"))
      (node (ref "R2_USB1") (pin "2") (pinfunction "2_2") (pintype "passive"))
    )
    (net (code "36") (name "Net-(J1-PadB5)") (class "Default")
      (node (ref "J1") (pin "B5") (pinfunction "B5_B5") (pintype "bidirectional"))
      (node (ref "R2_USB") (pin "1") (pinfunction "1_1") (pintype "passive"))
    )
    (net (code "37") (name "Net-(U1-PROG)") (class "Default")
      (node (ref "R2_BAT") (pin "2") (pinfunction "2_2") (pintype "passive"))
      (node (ref "U1") (pin "5") (pinfunction "PROG_5") (pintype "input"))
    )
    (net (code "38") (name "Net-(U1-STAT)") (class "Default")
      (node (ref "R1_BAT") (pin "2") (pinfunction "2_2") (pintype "passive"))
      (node (ref "U1") (pin "1") (pinfunction "STAT_1") (pintype "output"))
    )
    (net (code "39") (name "PREVGH") (class "Default")
      (node (ref "D5") (pin "1") (pinfunction "K_1") (pintype "bidirectional"))
      (node (ref "EPD_C9") (pin "2") (pinfunction "2_2") (pintype "passive"))
      (node (ref "J3") (pin "21") (pinfunction "21_21") (pintype "bidirectional"))
    )
    (net (code "40") (name "PREVGL") (class "Default")
      (node (ref "D4_") (pin "2") (pinfunction "A_2") (pintype "bidirectional"))
      (node (ref "EPD_C11") (pin "2") (pinfunction "2_2") (pintype "passive"))
      (node (ref "J3") (pin "23") (pinfunction "23_23") (pintype "bidirectional"))
    )
    (net (code "41") (name "RESE") (class "Default")
      (node (ref "J3") (pin "3") (pinfunction "3_3") (pintype "bidirectional"))
      (node (ref "Q2") (pin "2") (pinfunction "S_2") (pintype "bidirectional"))
      (node (ref "R2_") (pin "2") (pinfunction "2_2") (pintype "passive"))
      (node (ref "R3_") (pin "1") (pinfunction "1_1") (pintype "passive"))
      (node (ref "R3_") (pin "2") (pinfunction "2_2") (pintype "passive"))
      (node (ref "SJ1") (pin "2") (pinfunction "2_2") (pintype "passive"))
    )
    (net (code "42") (name "RESET") (class "Default")
      (node (ref "C5") (pin "1") (pinfunction "1_1") (pintype "passive"))
      (node (ref "IC2") (pin "1") (pinfunction "VOUT_1") (pintype "bidirectional"))
      (node (ref "RESET_BUTTON") (pin "3") (pinfunction "3_3") (pintype "passive"))
      (node (ref "RESET_BUTTON") (pin "4") (pinfunction "4_4") (pintype "passive"))
      (node (ref "R_RESET") (pin "1") (pinfunction "1_1") (pintype "passive"))
      (node (ref "U2") (pin "3") (pinfunction "EN_3") (pintype "input"))
    )
    (net (code "43") (name "RTC_RTS") (class "Default")
      (node (ref "U2") (pin "16") (pinfunction "IO18_16") (pintype "bidirectional"))
      (node (ref "U5") (pin "4") (pinfunction "~{RST}_4") (pintype "input"))
    )
    (net (code "44") (name "RX") (class "Default")
      (node (ref "TP2") (pin "TP") (pinfunction "TP_TP") (pintype "input"))
      (node (ref "U2") (pin "24") (pinfunction "RXD0/GPIO17_24") (pintype "bidirectional"))
    )
    (net (code "45") (name "SCK") (class "Default")
      (node (ref "D10_") (pin "2") (pinfunction "2_2") (pintype "passive"))
      (node (ref "J2") (pin "P5") (pinfunction "CLK_P5") (pintype "bidirectional"))
      (node (ref "J3") (pin "13") (pinfunction "13_13") (pintype "bidirectional"))
      (node (ref "R6") (pin "1") (pinfunction "1_1") (pintype "passive"))
      (node (ref "TP8") (pin "TP") (pinfunction "TP_TP") (pintype "input"))
      (node (ref "U2") (pin "6") (pinfunction "IO6_6") (pintype "bidirectional"))
      (node (ref "U6") (pin "6") (pinfunction "CLK_6") (pintype "input"))
    )
    (net (code "46") (name "SCL") (class "Default")
      (node (ref "J4") (pin "4") (pinfunction "4_4") (pintype "passive"))
      (node (ref "R2-PINH") (pin "1") (pinfunction "1_1") (pintype "passive"))
      (node (ref "SENSOR2") (pin "4") (pinfunction "SCK_4") (pintype "input"))
      (node (ref "U2") (pin "20") (pinfunction "IO22_20") (pintype "bidirectional"))
      (node (ref "U4") (pin "7") (pinfunction "SCL_7") (pintype "input"))
      (node (ref "U5") (pin "16") (pinfunction "SCL_16") (pintype "input"))
    )
    (net (code "47") (name "SDA") (class "Default")
      (node (ref "J4") (pin "3") (pinfunction "3_3") (pintype "passive"))
      (node (ref "R1_PINH") (pin "1") (pinfunction "1_1") (pintype "passive"))
      (node (ref "SENSOR2") (pin "3") (pinfunction "SDI_3") (pintype "bidirectional"))
      (node (ref "U2") (pin "19") (pinfunction "IO21_19") (pintype "bidirectional"))
      (node (ref "U4") (pin "8") (pinfunction "SDA_8") (pintype "bidirectional"))
      (node (ref "U5") (pin "15") (pinfunction "SDA_15") (pintype "bidirectional"))
    )
    (net (code "48") (name "SRC") (class "Default")
      (node (ref "C4_") (pin "2") (pinfunction "2_2") (pintype "passive"))
      (node (ref "D5") (pin "2") (pinfunction "A_2") (pintype "bidirectional"))
      (node (ref "L1") (pin "1") (pinfunction "1_1") (pintype "passive"))
      (node (ref "Q2") (pin "3") (pinfunction "D_3") (pintype "bidirectional"))
    )
    (net (code "49") (name "SS_SD") (class "Default")
      (node (ref "D8") (pin "2") (pinfunction "2_2") (pintype "passive"))
      (node (ref "J2") (pin "P2") (pinfunction "CD/DAT3_P2") (pintype "bidirectional"))
      (node (ref "R10_") (pin "1") (pinfunction "1_1") (pintype "passive"))
      (node (ref "U2") (pin "4") (pinfunction "IO4_4") (pintype "bidirectional"))
    )
    (net (code "50") (name "TX") (class "Default")
      (node (ref "TP1") (pin "TP") (pinfunction "TP_TP") (pintype "input"))
      (node (ref "U2") (pin "25") (pinfunction "TXD0/GPIO16_25") (pintype "bidirectional"))
    )
    (net (code "51") (name "USB_D+") (class "Default")
      (node (ref "D1") (pin "4") (pinfunction "I/O2_2_4") (pintype "bidirectional"))
      (node (ref "U2") (pin "14") (pinfunction "IO13_14") (pintype "bidirectional"))
    )
    (net (code "52") (name "USB_D-") (class "Default")
      (node (ref "D1") (pin "6") (pinfunction "I/O1_2_6") (pintype "bidirectional"))
      (node (ref "U2") (pin "13") (pinfunction "IO12_13") (pintype "bidirectional"))
    )
    (net (code "53") (name "VBAT") (class "Default")
      (node (ref "C2_BAT") (pin "1") (pinfunction "1_1") (pintype "passive"))
      (node (ref "Q1") (pin "3") (pinfunction "D_3") (pintype "bidirectional"))
      (node (ref "TP3") (pin "TP") (pinfunction "TP_TP") (pintype "input"))
      (node (ref "U1") (pin "3") (pinfunction "VBAT_3") (pintype "power_in"))
      (node (ref "U4") (pin "2") (pinfunction "CELL_2") (pintype "power_in"))
      (node (ref "U4") (pin "3") (pinfunction "VDD_3") (pintype "power_in"))
    )
    (net (code "54") (name "VBUS") (class "Default")
      (node (ref "C1_BAT") (pin "1") (pinfunction "1_1") (pintype "passive"))
      (node (ref "C4_USB") (pin "1") (pinfunction "1_1") (pintype "passive"))
      (node (ref "C5_USB") (pin "1") (pinfunction "1_1") (pintype "passive"))
      (node (ref "CHG_LED") (pin "A") (pinfunction "A_A") (pintype "passive"))
      (node (ref "D1") (pin "2") (pinfunction "GND_2") (pintype "bidirectional"))
      (node (ref "D2") (pin "2") (pinfunction "ANODE_2") (pintype "bidirectional"))
      (node (ref "Q1") (pin "1") (pinfunction "G_1") (pintype "bidirectional"))
      (node (ref "R1_PWRUSB") (pin "2") (pinfunction "2_2") (pintype "passive"))
      (node (ref "R2") (pin "2") (pinfunction "2_2") (pintype "passive"))
      (node (ref "TP14") (pin "TP") (pinfunction "TP_TP") (pintype "input"))
      (node (ref "U1") (pin "4") (pinfunction "VIN_4") (pintype "power_in"))
    )
    (net (code "55") (name "VRTC") (class "Default")
      (node (ref "C10_SUPERCAP") (pin "1") (pinfunction "1_1") (pintype "passive"))
      (node (ref "C8") (pin "1") (pinfunction "1_1") (pintype "passive"))
      (node (ref "R_CAPACITOR") (pin "2") (pinfunction "2_2") (pintype "passive"))
      (node (ref "U5") (pin "14") (pinfunction "VBAT_14") (pintype "power_in"))
    )
    (net (code "56") (name "VUSB") (class "Default")
      (node (ref "J1") (pin "A9") (pinfunction "A9_A9") (pintype "bidirectional"))
      (node (ref "J1") (pin "B4") (pinfunction "B4_B4") (pintype "bidirectional"))
      (node (ref "J1") (pin "B9") (pinfunction "B9_B9") (pintype "bidirectional"))
    )
    (net (code "57") (name "unconnected-(IC1-NC-Pad4)") (class "Default")
      (node (ref "IC1") (pin "4") (pinfunction "NC_4") (pintype "no_connect"))
    )
    (net (code "58") (name "unconnected-(IC2-NC-Pad4)") (class "Default")
      (node (ref "IC2") (pin "4") (pinfunction "NC_4") (pintype "no_connect"))
    )
    (net (code "59") (name "unconnected-(J1-PadA8)") (class "Default")
      (node (ref "J1") (pin "A8") (pinfunction "A8_A8") (pintype "bidirectional"))
    )
    (net (code "60") (name "unconnected-(J1-PadB8)") (class "Default")
      (node (ref "J1") (pin "B8") (pinfunction "B8_B8") (pintype "bidirectional"))
    )
    (net (code "61") (name "unconnected-(J2-DAT1-PadP8)") (class "Default")
      (node (ref "J2") (pin "P8") (pinfunction "DAT1_P8") (pintype "bidirectional"))
    )
    (net (code "62") (name "unconnected-(J2-DAT2-PadP1)") (class "Default")
      (node (ref "J2") (pin "P1") (pinfunction "DAT2_P1") (pintype "bidirectional"))
    )
    (net (code "63") (name "unconnected-(J2-DETECTION_1-PadS1)") (class "Default")
      (node (ref "J2") (pin "S1") (pinfunction "DETECTION_1_S1") (pintype "bidirectional"))
    )
    (net (code "64") (name "unconnected-(J2-DETECTION_2-PadS2)") (class "Default")
      (node (ref "J2") (pin "S2") (pinfunction "DETECTION_2_S2") (pintype "bidirectional"))
    )
    (net (code "65") (name "unconnected-(J3-Pad1)") (class "Default")
      (node (ref "J3") (pin "1") (pinfunction "1_1") (pintype "bidirectional"))
    )
    (net (code "66") (name "unconnected-(J3-Pad6)") (class "Default")
      (node (ref "J3") (pin "6") (pinfunction "6_6") (pintype "bidirectional"))
    )
    (net (code "67") (name "unconnected-(J3-Pad7)") (class "Default")
      (node (ref "J3") (pin "7") (pinfunction "7_7") (pintype "bidirectional"))
    )
    (net (code "68") (name "unconnected-(U2-NC-Pad22)") (class "Default")
      (node (ref "U2") (pin "22") (pinfunction "NC_22") (pintype "no_connect"))
    )
    (net (code "69") (name "unconnected-(U4-~{ALERT}-Pad5)") (class "Default")
      (node (ref "U4") (pin "5") (pinfunction "~{ALERT}_5") (pintype "output"))
    )
  )
)
